# ATMega32U4.net
KiCad netlist of a schematic drawn in Altium Designer
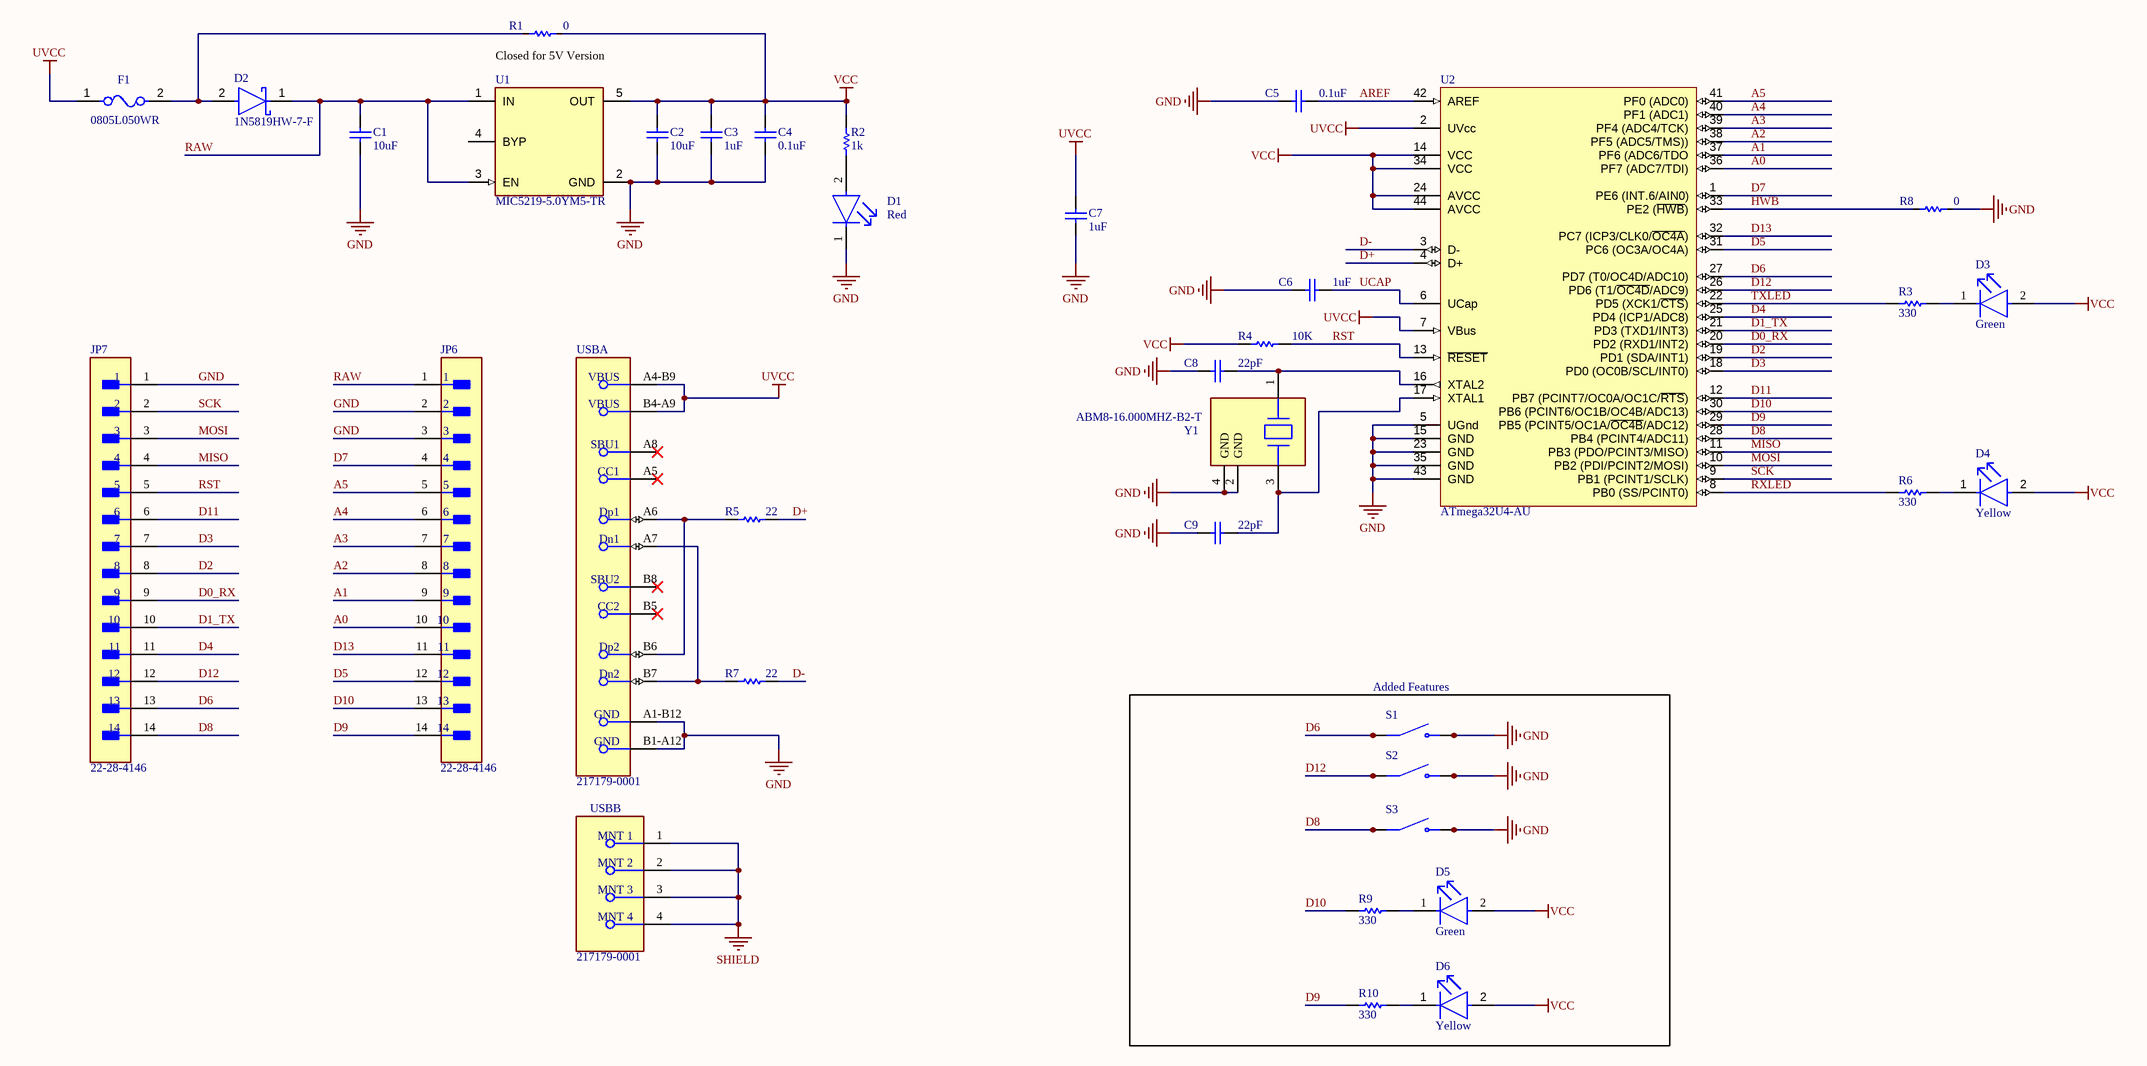
[diagram p0: ATMega32U4.SchDoc]

(export (version "E")
  (design (tool "Eeschema 10.0.6"))
  (components
    (comp (ref "C1")
      (value "CAP GENERIC 0603")
      (footprint "CAPC1608X09L")
      (fields
        (field (name "MANUFACTURER PART NUMBER") "GRM188R61C106MAALD")
        (field (name "CAPACITANCE") "10uF")
      )
      (libsource (lib "Generic Capacitors") (part "CAP0603"))
    )
    (comp (ref "C2")
      (value "CAP GENERIC 0603")
      (footprint "CAPC1608X09L")
      (fields
        (field (name "MANUFACTURER PART NUMBER") "GRM188R61C106MAALD")
        (field (name "CAPACITANCE") "10uF")
      )
      (libsource (lib "Generic Capacitors") (part "CAP0603"))
    )
    (comp (ref "C3")
      (value "CAP GENERIC 0603")
      (footprint "CAPC1608X09L")
      (fields
        (field (name "MANUFACTURER PART NUMBER") "GCM188R71E105KA64D")
        (field (name "CAPACITANCE") "1uF")
      )
      (libsource (lib "Generic Capacitors") (part "CAP0603"))
    )
    (comp (ref "C4")
      (value "CAP GENERIC 0603")
      (footprint "CAPC1608X09L")
      (fields
        (field (name "MANUFACTURER PART NUMBER") "GCM188R71H104KA57D")
        (field (name "CAPACITANCE") "0.1uF")
      )
      (libsource (lib "Generic Capacitors") (part "CAP0603"))
    )
    (comp (ref "C5")
      (value "CAP GENERIC 0603")
      (footprint "CAPC1608X09L")
      (fields
        (field (name "MANUFACTURER PART NUMBER") "GCM188R71H104KA57D")
        (field (name "CAPACITANCE") "0.1uF")
      )
      (libsource (lib "Generic Capacitors") (part "CAP0603"))
    )
    (comp (ref "C6")
      (value "CAP GENERIC 0603")
      (footprint "CAPC1608X09L")
      (fields
        (field (name "MANUFACTURER PART NUMBER") "GCM188R71E105KA64D")
        (field (name "CAPACITANCE") "1uF")
      )
      (libsource (lib "Generic Capacitors") (part "CAP0603"))
    )
    (comp (ref "C7")
      (value "CAP GENERIC 0603")
      (footprint "CAPC1608X09L")
      (fields
        (field (name "MANUFACTURER PART NUMBER") "GCM188R71E105KA64D")
        (field (name "CAPACITANCE") "1uF")
      )
      (libsource (lib "Generic Capacitors") (part "CAP0603"))
    )
    (comp (ref "C8")
      (value "CAP GENERIC 0603")
      (footprint "CAPC1608X09L")
      (fields
        (field (name "MANUFACTURER PART NUMBER") "GCM1885C2A220FA16D")
        (field (name "CAPACITANCE") "22pF")
      )
      (libsource (lib "Generic Capacitors") (part "CAP0603"))
    )
    (comp (ref "C9")
      (value "CAP GENERIC 0603")
      (footprint "CAPC1608X09L")
      (fields
        (field (name "MANUFACTURER PART NUMBER") "GCM1885C2A220FA16D")
        (field (name "CAPACITANCE") "22pF")
      )
      (libsource (lib "Generic Capacitors") (part "CAP0603"))
    )
    (comp (ref "D1")
      (value "Red")
      (footprint "FP-LTST-C191KRKT-MFG")
      (fields
        (field (name "VOLTAGE") "2V")
        (field (name "MANUFACTURER") "Vishay Lite-On")
        (field (name "MANUFACTURER PART NUMBER") "LTST-C191KRKT")
      )
      (libsource (lib "Altium Content Vault") (part "8706943c75ba83719d021d2fdc84c58"))
    )
    (comp (ref "D2")
      (value "1N5819HW-7-F")
      (footprint "FP-SOD123-IPC_A")
      (description "DIODE SCHOTTKY 40V 1A SOD123")
      (fields (field (name "MANUFACTURER") "Diodes"))
      (libsource (lib "Altium Content Vault") (part "1d6ec82d83fb6aee721767c19dac4b9"))
    )
    (comp (ref "D3")
      (value "Green")
      (footprint "FP-LTST-C191KGKT-MFG")
      (description "LED GREEN CLEAR SMD")
      (fields
        (field (name "MANUFACTURER") "Vishay Lite-On")
        (field (name "MANUFACTURER PART NUMBER") "LTST-C191KGKT")
      )
      (libsource (lib "Altium Content Vault") (part "8706943c75ba83719d021d2fdc84c58"))
    )
    (comp (ref "D4")
      (value "Yellow")
      (footprint "FP-LTST-C191KSKT-MFG")
      (description "LED YELLOW CLEAR SMD")
      (fields
        (field (name "MANUFACTURER") "Vishay Lite-On")
        (field (name "MANUFACTURER PART NUMBER") "LTST-C191KSKT")
      )
      (libsource (lib "Altium Content Vault") (part "8706943c75ba83719d021d2fdc84c58"))
    )
    (comp (ref "D5")
      (value "Green")
      (footprint "FP-LTST-C191KGKT-MFG")
      (description "LED GREEN CLEAR SMD")
      (fields
        (field (name "MANUFACTURER") "Vishay Lite-On")
        (field (name "MANUFACTURER PART NUMBER") "LTST-C191KGKT")
      )
      (libsource (lib "Altium Content Vault") (part "8706943c75ba83719d021d2fdc84c58"))
    )
    (comp (ref "D6")
      (value "Yellow")
      (footprint "FP-LTST-C191KSKT-MFG")
      (description "LED YELLOW CLEAR SMD")
      (fields
        (field (name "MANUFACTURER") "Vishay Lite-On")
        (field (name "MANUFACTURER PART NUMBER") "LTST-C191KSKT")
      )
      (libsource (lib "Altium Content Vault") (part "8706943c75ba83719d021d2fdc84c58"))
    )
    (comp (ref "F1")
      (value "0805L050WR")
      (footprint "FP-0805L-MFG")
      (description "PTC RESET FUSE 6V 500MA 0805")
      (fields
        (field (name "MANUFACTURER") "Littelfuse Inc.")
        (field (name "OCTOPART") "https://octopart.com/0805l050wr-littelfuse-673858")
      )
      (libsource (lib "Altium Content Vault") (part "5bcf9b9f640e542cf0359d10258e979"))
    )
    (comp (ref "JP6")
      (value "22-28-4146")
      (footprint "FP-22-28-4146-MFG")
      (description "CONN HEADER VERT 14POS 2.54MM")
      (fields (field (name "MANUFACTURER") "Molex"))
      (libsource (lib "") (part "22-28-4146_1"))
    )
    (comp (ref "JP7")
      (value "22-28-4146")
      (footprint "FP-22-28-4146-MFG")
      (description "CONN HEADER VERT 14POS 2.54MM")
      (fields (field (name "MANUFACTURER") "Molex"))
      (libsource (lib "Shadowfang_Proj") (part "22-28-4146"))
    )
    (comp (ref "R1")
      (value "0")
      (footprint "RES_0603")
      (description "Metal Glaze/thick Film, 0.1W, 0ohm, Surface Mount, 0603")
      (fields
        (field (name "MANUFACTURER") "Vishay")
        (field (name "MANUFACTURER PART NUMBER") "CRCW06030000Z0EA")
        (field (name "RESISTANCE") "0")
      )
      (libsource (lib "Resistors") (part "CRCW06030000Z0EA"))
    )
    (comp (ref "R2")
      (value "GENERIC 0603 RESISTOR")
      (footprint "RESC1608X06L")
      (fields
        (field (name "MANUFACTURER PART NUMBER") "CRCW06031K00FKEAHP")
        (field (name "RESISTANCE (OHMS)") "1k")
      )
      (libsource (lib "Generic Resistors") (part "RES0603"))
    )
    (comp (ref "R3")
      (value "GENERIC 0603 RESISTOR")
      (footprint "RESC1608X06L")
      (fields
        (field (name "MANUFACTURER PART NUMBER") "CRCW0603330RFKEAHP")
        (field (name "RESISTANCE (OHMS)") "330")
      )
      (libsource (lib "Generic Resistors") (part "RES0603"))
    )
    (comp (ref "R4")
      (value "GENERIC 0603 RESISTOR")
      (footprint "RESC1608X06L")
      (fields
        (field (name "MANUFACTURER PART NUMBER") "CRCW060310K0FKEAHP")
        (field (name "RESISTANCE (OHMS)") "10K")
      )
      (libsource (lib "Generic Resistors") (part "RES0603"))
    )
    (comp (ref "R5")
      (value "GENERIC 0603 RESISTOR")
      (footprint "RESC1608X06L")
      (fields
        (field (name "MANUFACTURER PART NUMBER") "CRCW060322R0JNEAHP")
        (field (name "RESISTANCE (OHMS)") "22")
      )
      (libsource (lib "Generic Resistors") (part "RES0603"))
    )
    (comp (ref "R6")
      (value "GENERIC 0603 RESISTOR")
      (footprint "RESC1608X06L")
      (fields
        (field (name "MANUFACTURER PART NUMBER") "CRCW0603330RFKEAHP")
        (field (name "RESISTANCE (OHMS)") "330")
      )
      (libsource (lib "Generic Resistors") (part "RES0603"))
    )
    (comp (ref "R7")
      (value "GENERIC 0603 RESISTOR")
      (footprint "RESC1608X06L")
      (fields
        (field (name "MANUFACTURER PART NUMBER") "CRCW060322R0JNEAHP")
        (field (name "RESISTANCE (OHMS)") "22")
      )
      (libsource (lib "Generic Resistors") (part "RES0603"))
    )
    (comp (ref "R8")
      (value "0")
      (footprint "RES_0603")
      (description "Metal Glaze/thick Film, 0.1W, 0ohm, Surface Mount, 0603")
      (fields
        (field (name "MANUFACTURER") "Vishay")
        (field (name "MANUFACTURER PART NUMBER") "CRCW06030000Z0EA")
        (field (name "RESISTANCE") "0")
      )
      (libsource (lib "Resistors") (part "CRCW06030000Z0EA"))
    )
    (comp (ref "R9")
      (value "GENERIC 0603 RESISTOR")
      (footprint "RESC1608X06L")
      (fields
        (field (name "MANUFACTURER PART NUMBER") "CRCW0603330RFKEAHP")
        (field (name "RESISTANCE (OHMS)") "330")
      )
      (libsource (lib "Generic Resistors") (part "RES0603"))
    )
    (comp (ref "R10")
      (value "GENERIC 0603 RESISTOR")
      (footprint "RESC1608X06L")
      (fields
        (field (name "MANUFACTURER PART NUMBER") "CRCW0603330RFKEAHP")
        (field (name "RESISTANCE (OHMS)") "330")
      )
      (libsource (lib "Generic Resistors") (part "RES0603"))
    )
    (comp (ref "S1")
      (value "PTS_647_SN50_SMTR2_LFS")
      (footprint "SW_PTS_647_SN50_SMTR2_LFS")
      (description "Tactile Switch SPST-NO Top Actuated Surface Mount")
      (fields (field (name "MF") "C&K") (field (name "MP") "PTS 647 SN50 SMTR2 LFS"))
      (libsource (lib "Shadowfang_Proj") (part "PTS_647_SN50_SMTR2_LFS"))
    )
    (comp (ref "S2")
      (value "PTS_647_SN50_SMTR2_LFS")
      (footprint "SW_PTS_647_SN50_SMTR2_LFS")
      (description "Tactile Switch SPST-NO Top Actuated Surface Mount")
      (fields (field (name "MF") "C&K") (field (name "MP") "PTS 647 SN50 SMTR2 LFS"))
      (libsource (lib "Shadowfang_Proj") (part "PTS_647_SN50_SMTR2_LFS"))
    )
    (comp (ref "S3")
      (value "PTS_647_SN50_SMTR2_LFS")
      (footprint "SW_PTS_647_SN50_SMTR2_LFS")
      (description "Tactile Switch SPST-NO Top Actuated Surface Mount")
      (fields (field (name "MF") "C&K") (field (name "MP") "PTS 647 SN50 SMTR2 LFS"))
      (libsource (lib "Shadowfang_Proj") (part "PTS_647_SN50_SMTR2_LFS"))
    )
    (comp (ref "U1")
      (value "MIC5219-5.0YM5-TR")
      (footprint "FP-SOT23-5LD-PL-1-MFG")
      (description "IC REG LINEAR 5V 500MA SOT23-5")
      (fields
        (field (name "OCTOPART") "https://octopart.com/mic5219-5.0ym5-tr-microchip-66802269")
        (field (name "MANUFACTURER") "Microchip Technology")
      )
      (libsource (lib "Altium Content Vault") (part "ef5decc81e5e4ee52dbbc9c70b739cf"))
    )
    (comp (ref "U2")
      (value "ATmega32U4-AU")
      (footprint "44ML_M")
      (fields
        (field (name "MANUFACTURER") "Microchip")
        (field (name "MANUFACTURER PART NUMBER") "ATMEGA32U4-AU")
      )
      (libsource (lib "Altium Content Vault") (part "MC-8B-ATM16U4-SQ44"))
    )
    (comp (ref "USB")
      (value "217179-0001")
      (footprint "FP-2171790001-MFG")
      (description "CONN RCP USB2.0 TYP C 24P SMD RA")
      (fields (field (name "MANUFACTURER PART NUMBER") "2171790001"))
      (libsource (lib "Altium Content Vault") (part "8b86497a633d14b3f74642136fc0ce6"))
    )
    (comp (ref "Y1")
      (value "ABM8-16.000MHZ-B2-T")
      (footprint "FP-ABM8-MFG")
      (description "Crystal 16MHz ±20ppm 18pF SMD-4 3.2mm x 2.5mm")
      (fields (field (name "TOLERANCE") "20ppm") (field (name "MANUFACTURER") "Abracon"))
      (libsource (lib "Altium Content Vault") (part "dfdb7f9a12507849fb681da9a70121c"))
    )
  )
  (nets
    (net (code "1") (name "/A0") (class "Default")
      (node (ref "JP6") (pin "10") (pinfunction "10_10") (pintype "passive"))
      (node (ref "U2") (pin "36") (pinfunction "PF7_(ADC7/TDI)_36") (pintype "bidirectional"))
    )
    (net (code "2") (name "/A1") (class "Default")
      (node (ref "JP6") (pin "9") (pinfunction "9_9") (pintype "passive"))
      (node (ref "U2") (pin "37") (pinfunction "PF6_(ADC6/TDO_37") (pintype "bidirectional"))
    )
    (net (code "3") (name "/A2") (class "Default")
      (node (ref "JP6") (pin "8") (pinfunction "8_8") (pintype "passive"))
      (node (ref "U2") (pin "38") (pinfunction "PF5_(ADC5/TMS))_38") (pintype "bidirectional"))
    )
    (net (code "4") (name "/A3") (class "Default")
      (node (ref "JP6") (pin "7") (pinfunction "7_7") (pintype "passive"))
      (node (ref "U2") (pin "39") (pinfunction "PF4_(ADC4/TCK)_39") (pintype "bidirectional"))
    )
    (net (code "5") (name "/A4") (class "Default")
      (node (ref "JP6") (pin "6") (pinfunction "6_6") (pintype "passive"))
      (node (ref "U2") (pin "40") (pinfunction "PF1_(ADC1)_40") (pintype "bidirectional"))
    )
    (net (code "6") (name "/A5") (class "Default")
      (node (ref "JP6") (pin "5") (pinfunction "5_5") (pintype "passive"))
      (node (ref "U2") (pin "41") (pinfunction "PF0_(ADC0)_41") (pintype "bidirectional"))
    )
    (net (code "7") (name "/AREF") (class "Default")
      (node (ref "C5") (pin "2") (pinfunction "2_2") (pintype "passive"))
      (node (ref "U2") (pin "42") (pinfunction "AREF_42") (pintype "input"))
    )
    (net (code "8") (name "/D+") (class "Default")
      (node (ref "R5") (pin "2") (pinfunction "2_2") (pintype "passive"))
      (node (ref "U2") (pin "4") (pinfunction "D+_4") (pintype "bidirectional"))
    )
    (net (code "9") (name "/D-") (class "Default")
      (node (ref "R7") (pin "2") (pinfunction "2_2") (pintype "passive"))
      (node (ref "U2") (pin "3") (pinfunction "D-_3") (pintype "bidirectional"))
    )
    (net (code "10") (name "/D0_RX") (class "Default")
      (node (ref "JP7") (pin "9") (pinfunction "9_9") (pintype "passive"))
      (node (ref "U2") (pin "20") (pinfunction "PD2_(RXD1/INT2)_20") (pintype "bidirectional"))
    )
    (net (code "11") (name "/D1_TX") (class "Default")
      (node (ref "JP7") (pin "10") (pinfunction "10_10") (pintype "passive"))
      (node (ref "U2") (pin "21") (pinfunction "PD3_(TXD1/INT3)_21") (pintype "bidirectional"))
    )
    (net (code "12") (name "/D2") (class "Default")
      (node (ref "JP7") (pin "8") (pinfunction "8_8") (pintype "passive"))
      (node (ref "U2") (pin "19") (pinfunction "PD1_(SDA/INT1)_19") (pintype "bidirectional"))
    )
    (net (code "13") (name "/D3") (class "Default")
      (node (ref "JP7") (pin "7") (pinfunction "7_7") (pintype "passive"))
      (node (ref "U2") (pin "18") (pinfunction "PD0_(OC0B/SCL/INT0)_18") (pintype "bidirectional"))
    )
    (net (code "14") (name "/D4") (class "Default")
      (node (ref "JP7") (pin "11") (pinfunction "11_11") (pintype "passive"))
      (node (ref "U2") (pin "25") (pinfunction "PD4_(ICP1/ADC8)_25") (pintype "bidirectional"))
    )
    (net (code "15") (name "/D5") (class "Default")
      (node (ref "JP6") (pin "12") (pinfunction "12_12") (pintype "passive"))
      (node (ref "U2") (pin "31") (pinfunction "PC6_(OC3A/OC4A)_31") (pintype "bidirectional"))
    )
    (net (code "16") (name "/D6") (class "Default")
      (node (ref "JP7") (pin "13") (pinfunction "13_13") (pintype "passive"))
      (node (ref "S1") (pin "3") (pinfunction "COM_3") (pintype "passive"))
      (node (ref "S1") (pin "4") (pinfunction "COM_4") (pintype "passive"))
      (node (ref "U2") (pin "27") (pinfunction "PD7_(T0/OC4D/ADC10)_27") (pintype "bidirectional"))
    )
    (net (code "17") (name "/D7") (class "Default")
      (node (ref "JP6") (pin "4") (pinfunction "4_4") (pintype "passive"))
      (node (ref "U2") (pin "1") (pinfunction "PE6_(INT.6/AIN0)_1") (pintype "bidirectional"))
    )
    (net (code "18") (name "/D8") (class "Default")
      (node (ref "JP7") (pin "14") (pinfunction "14_14") (pintype "passive"))
      (node (ref "S3") (pin "3") (pinfunction "COM_3") (pintype "passive"))
      (node (ref "S3") (pin "4") (pinfunction "COM_4") (pintype "passive"))
      (node (ref "U2") (pin "28") (pinfunction "PB4_(PCINT4/ADC11)_28") (pintype "bidirectional"))
    )
    (net (code "19") (name "/D9") (class "Default")
      (node (ref "JP6") (pin "14") (pinfunction "14_14") (pintype "passive"))
      (node (ref "R10") (pin "1") (pinfunction "1_1") (pintype "passive"))
      (node (ref "U2") (pin "29") (pinfunction "PB5_(PCINT5/OC1A/~{OC4B}/ADC12)_29") (pintype "bidirectional"))
    )
    (net (code "20") (name "/D10") (class "Default")
      (node (ref "JP6") (pin "13") (pinfunction "13_13") (pintype "passive"))
      (node (ref "R9") (pin "1") (pinfunction "1_1") (pintype "passive"))
      (node (ref "U2") (pin "30") (pinfunction "PB6_(PCINT6/OC1B/OC4B/ADC13)_30") (pintype "bidirectional"))
    )
    (net (code "21") (name "/D11") (class "Default")
      (node (ref "JP7") (pin "6") (pinfunction "6_6") (pintype "passive"))
      (node (ref "U2") (pin "12") (pinfunction "PB7_(PCINT7/OC0A/OC1C/~{RTS})_12") (pintype "bidirectional"))
    )
    (net (code "22") (name "/D12") (class "Default")
      (node (ref "JP7") (pin "12") (pinfunction "12_12") (pintype "passive"))
      (node (ref "S2") (pin "3") (pinfunction "COM_3") (pintype "passive"))
      (node (ref "S2") (pin "4") (pinfunction "COM_4") (pintype "passive"))
      (node (ref "U2") (pin "26") (pinfunction "PD6_(T1/~{OC4D}/ADC9)_26") (pintype "bidirectional"))
    )
    (net (code "23") (name "/D13") (class "Default")
      (node (ref "JP6") (pin "11") (pinfunction "11_11") (pintype "passive"))
      (node (ref "U2") (pin "32") (pinfunction "PC7_(ICP3/CLK0/~{OC4A})_32") (pintype "bidirectional"))
    )
    (net (code "24") (name "/HWB") (class "Default")
      (node (ref "R8") (pin "1") (pinfunction "1_1") (pintype "passive"))
      (node (ref "U2") (pin "33") (pinfunction "PE2_(~{HWB})_33") (pintype "bidirectional"))
    )
    (net (code "25") (name "/MISO") (class "Default")
      (node (ref "JP7") (pin "4") (pinfunction "4_4") (pintype "passive"))
      (node (ref "U2") (pin "11") (pinfunction "PB3_(PDO/PCINT3/MISO)_11") (pintype "bidirectional"))
    )
    (net (code "26") (name "/MOSI") (class "Default")
      (node (ref "JP7") (pin "3") (pinfunction "3_3") (pintype "passive"))
      (node (ref "U2") (pin "10") (pinfunction "PB2_(PDI/PCINT2/MOSI)_10") (pintype "bidirectional"))
    )
    (net (code "27") (name "/RAW") (class "Default")
      (node (ref "C1") (pin "2") (pinfunction "2_2") (pintype "passive"))
      (node (ref "D2") (pin "1") (pinfunction "C_1") (pintype "passive"))
      (node (ref "JP6") (pin "1") (pinfunction "1_1") (pintype "passive"))
      (node (ref "U1") (pin "1") (pinfunction "IN_1") (pintype "power_in"))
      (node (ref "U1") (pin "3") (pinfunction "EN_3") (pintype "input"))
    )
    (net (code "28") (name "/RST") (class "Default")
      (node (ref "JP7") (pin "5") (pinfunction "5_5") (pintype "passive"))
      (node (ref "R4") (pin "2") (pinfunction "2_2") (pintype "passive"))
      (node (ref "U2") (pin "13") (pinfunction "~{RESET}_13") (pintype "input"))
    )
    (net (code "29") (name "/RXLED") (class "Default")
      (node (ref "R6") (pin "1") (pinfunction "1_1") (pintype "passive"))
      (node (ref "U2") (pin "8") (pinfunction "PB0_(SS/PCINT0)_8") (pintype "bidirectional"))
    )
    (net (code "30") (name "/SCK") (class "Default")
      (node (ref "JP7") (pin "2") (pinfunction "2_2") (pintype "passive"))
      (node (ref "U2") (pin "9") (pinfunction "PB1_(PCINT1/SCLK)_9") (pintype "bidirectional"))
    )
    (net (code "31") (name "/TXLED") (class "Default")
      (node (ref "R3") (pin "1") (pinfunction "1_1") (pintype "passive"))
      (node (ref "U2") (pin "22") (pinfunction "PD5_(XCK1/~{CTS})_22") (pintype "bidirectional"))
    )
    (net (code "32") (name "/UCAP") (class "Default")
      (node (ref "C6") (pin "2") (pinfunction "2_2") (pintype "passive"))
      (node (ref "U2") (pin "6") (pinfunction "UCap_6") (pintype "passive"))
    )
    (net (code "33") (name "GND") (class "Default")
      (node (ref "C1") (pin "1") (pinfunction "1_1") (pintype "passive"))
      (node (ref "C2") (pin "1") (pinfunction "1_1") (pintype "passive"))
      (node (ref "C3") (pin "1") (pinfunction "1_1") (pintype "passive"))
      (node (ref "C4") (pin "1") (pinfunction "1_1") (pintype "passive"))
      (node (ref "C5") (pin "1") (pinfunction "1_1") (pintype "passive"))
      (node (ref "C6") (pin "1") (pinfunction "1_1") (pintype "passive"))
      (node (ref "C7") (pin "1") (pinfunction "1_1") (pintype "passive"))
      (node (ref "C8") (pin "1") (pinfunction "1_1") (pintype "passive"))
      (node (ref "C9") (pin "1") (pinfunction "1_1") (pintype "passive"))
      (node (ref "D1") (pin "1") (pinfunction "C_1") (pintype "passive"))
      (node (ref "JP6") (pin "2") (pinfunction "2_2") (pintype "passive"))
      (node (ref "JP6") (pin "3") (pinfunction "3_3") (pintype "passive"))
      (node (ref "JP7") (pin "1") (pinfunction "1_1") (pintype "passive"))
      (node (ref "R8") (pin "2") (pinfunction "2_2") (pintype "passive"))
      (node (ref "S1") (pin "1") (pinfunction "NO_1") (pintype "passive"))
      (node (ref "S1") (pin "2") (pinfunction "NO_2") (pintype "passive"))
      (node (ref "S2") (pin "1") (pinfunction "NO_1") (pintype "passive"))
      (node (ref "S2") (pin "2") (pinfunction "NO_2") (pintype "passive"))
      (node (ref "S3") (pin "1") (pinfunction "NO_1") (pintype "passive"))
      (node (ref "S3") (pin "2") (pinfunction "NO_2") (pintype "passive"))
      (node (ref "U1") (pin "2") (pinfunction "GND_2") (pintype "power_in"))
      (node (ref "U2") (pin "15") (pinfunction "GND_15") (pintype "power_in"))
      (node (ref "U2") (pin "23") (pinfunction "GND_23") (pintype "power_in"))
      (node (ref "U2") (pin "35") (pinfunction "GND_35") (pintype "power_in"))
      (node (ref "U2") (pin "43") (pinfunction "GND_43") (pintype "power_in"))
      (node (ref "U2") (pin "5") (pinfunction "UGnd_5") (pintype "power_in"))
      (node (ref "USB") (pin "A1-B12") (pinfunction "GND_A1-B12") (pintype "power_in"))
      (node (ref "USB") (pin "B1-A12") (pinfunction "GND_B1-A12") (pintype "power_in"))
      (node (ref "Y1") (pin "2") (pinfunction "GND_2") (pintype "power_in"))
      (node (ref "Y1") (pin "4") (pinfunction "GND_4") (pintype "power_in"))
    )
    (net (code "34") (name "Net-(D1-A)") (class "Default")
      (node (ref "D1") (pin "2") (pinfunction "A_2") (pintype "passive"))
      (node (ref "R2") (pin "1") (pinfunction "1_1") (pintype "passive"))
    )
    (net (code "35") (name "Net-(D2-A)") (class "Default")
      (node (ref "D2") (pin "2") (pinfunction "A_2") (pintype "passive"))
      (node (ref "F1") (pin "2") (pinfunction "2_2") (pintype "passive"))
      (node (ref "R1") (pin "1") (pinfunction "1_1") (pintype "passive"))
    )
    (net (code "36") (name "Net-(D3-C)") (class "Default")
      (node (ref "D3") (pin "1") (pinfunction "C_1") (pintype "passive"))
      (node (ref "R3") (pin "2") (pinfunction "2_2") (pintype "passive"))
    )
    (net (code "37") (name "Net-(D4-C)") (class "Default")
      (node (ref "D4") (pin "1") (pinfunction "C_1") (pintype "passive"))
      (node (ref "R6") (pin "2") (pinfunction "2_2") (pintype "passive"))
    )
    (net (code "38") (name "Net-(D5-C)") (class "Default")
      (node (ref "D5") (pin "1") (pinfunction "C_1") (pintype "passive"))
      (node (ref "R9") (pin "2") (pinfunction "2_2") (pintype "passive"))
    )
    (net (code "39") (name "Net-(D6-C)") (class "Default")
      (node (ref "D6") (pin "1") (pinfunction "C_1") (pintype "passive"))
      (node (ref "R10") (pin "2") (pinfunction "2_2") (pintype "passive"))
    )
    (net (code "40") (name "Net-(U2-XTAL1)") (class "Default")
      (node (ref "C9") (pin "2") (pinfunction "2_2") (pintype "passive"))
      (node (ref "U2") (pin "17") (pinfunction "XTAL1_17") (pintype "input"))
      (node (ref "Y1") (pin "3") (pinfunction "3_3") (pintype "passive"))
    )
    (net (code "41") (name "Net-(U2-XTAL2)") (class "Default")
      (node (ref "C8") (pin "2") (pinfunction "2_2") (pintype "passive"))
      (node (ref "U2") (pin "16") (pinfunction "XTAL2_16") (pintype "output"))
      (node (ref "Y1") (pin "1") (pinfunction "1_1") (pintype "passive"))
    )
    (net (code "42") (name "Net-(USBA-Dn1)") (class "Default")
      (node (ref "R7") (pin "1") (pinfunction "1_1") (pintype "passive"))
      (node (ref "USB") (pin "A7") (pinfunction "Dn1_A7") (pintype "bidirectional"))
      (node (ref "USB") (pin "B7") (pinfunction "Dn2_B7") (pintype "bidirectional"))
    )
    (net (code "43") (name "Net-(USBA-Dp1)") (class "Default")
      (node (ref "R5") (pin "1") (pinfunction "1_1") (pintype "passive"))
      (node (ref "USB") (pin "A6") (pinfunction "Dp1_A6") (pintype "bidirectional"))
      (node (ref "USB") (pin "B6") (pinfunction "Dp2_B6") (pintype "bidirectional"))
    )
    (net (code "44") (name "SHIELD") (class "Default")
      (node (ref "USB") (pin "1") (pinfunction "MNT_1_1") (pintype "passive"))
      (node (ref "USB") (pin "2") (pinfunction "MNT_2_2") (pintype "passive"))
      (node (ref "USB") (pin "3") (pinfunction "MNT_3_3") (pintype "power_in"))
      (node (ref "USB") (pin "4") (pinfunction "MNT_4_4") (pintype "power_in"))
    )
    (net (code "45") (name "UVCC") (class "Default")
      (node (ref "C7") (pin "2") (pinfunction "2_2") (pintype "passive"))
      (node (ref "F1") (pin "1") (pinfunction "1_1") (pintype "passive"))
      (node (ref "U2") (pin "2") (pinfunction "UVcc_2") (pintype "power_in"))
      (node (ref "U2") (pin "7") (pinfunction "VBus_7") (pintype "input"))
      (node (ref "USB") (pin "A4-B9") (pinfunction "VBUS_A4-B9") (pintype "power_in"))
      (node (ref "USB") (pin "B4-A9") (pinfunction "VBUS_B4-A9") (pintype "power_in"))
    )
    (net (code "46") (name "VCC") (class "Default")
      (node (ref "C2") (pin "2") (pinfunction "2_2") (pintype "passive"))
      (node (ref "C3") (pin "2") (pinfunction "2_2") (pintype "passive"))
      (node (ref "C4") (pin "2") (pinfunction "2_2") (pintype "passive"))
      (node (ref "D3") (pin "2") (pinfunction "A_2") (pintype "passive"))
      (node (ref "D4") (pin "2") (pinfunction "A_2") (pintype "passive"))
      (node (ref "D5") (pin "2") (pinfunction "A_2") (pintype "passive"))
      (node (ref "D6") (pin "2") (pinfunction "A_2") (pintype "passive"))
      (node (ref "R1") (pin "2") (pinfunction "2_2") (pintype "passive"))
      (node (ref "R2") (pin "2") (pinfunction "2_2") (pintype "passive"))
      (node (ref "R4") (pin "1") (pinfunction "1_1") (pintype "passive"))
      (node (ref "U1") (pin "5") (pinfunction "OUT_5") (pintype "power_in"))
      (node (ref "U2") (pin "14") (pinfunction "VCC_14") (pintype "power_in"))
      (node (ref "U2") (pin "24") (pinfunction "AVCC_24") (pintype "power_in"))
      (node (ref "U2") (pin "34") (pinfunction "VCC_34") (pintype "power_in"))
      (node (ref "U2") (pin "44") (pinfunction "AVCC_44") (pintype "power_in"))
    )
    (net (code "47") (name "unconnected-(U1-BYP-Pad4)") (class "Default")
      (node (ref "U1") (pin "4") (pinfunction "BYP_4") (pintype "passive"))
    )
    (net (code "48") (name "unconnected-(USBA-CC1-PadA5)") (class "Default")
      (node (ref "USB") (pin "A5") (pinfunction "CC1_A5") (pintype "passive+no_connect"))
    )
    (net (code "49") (name "unconnected-(USBA-CC2-PadB5)") (class "Default")
      (node (ref "USB") (pin "B5") (pinfunction "CC2_B5") (pintype "passive+no_connect"))
    )
    (net (code "50") (name "unconnected-(USBA-SBU1-PadA8)") (class "Default")
      (node (ref "USB") (pin "A8") (pinfunction "SBU1_A8") (pintype "passive+no_connect"))
    )
    (net (code "51") (name "unconnected-(USBA-SBU2-PadB8)") (class "Default")
      (node (ref "USB") (pin "B8") (pinfunction "SBU2_B8") (pintype "passive+no_connect"))
    )
  )
)
